# PowerSupply.net
KiCad netlist of a schematic drawn in Altium Designer
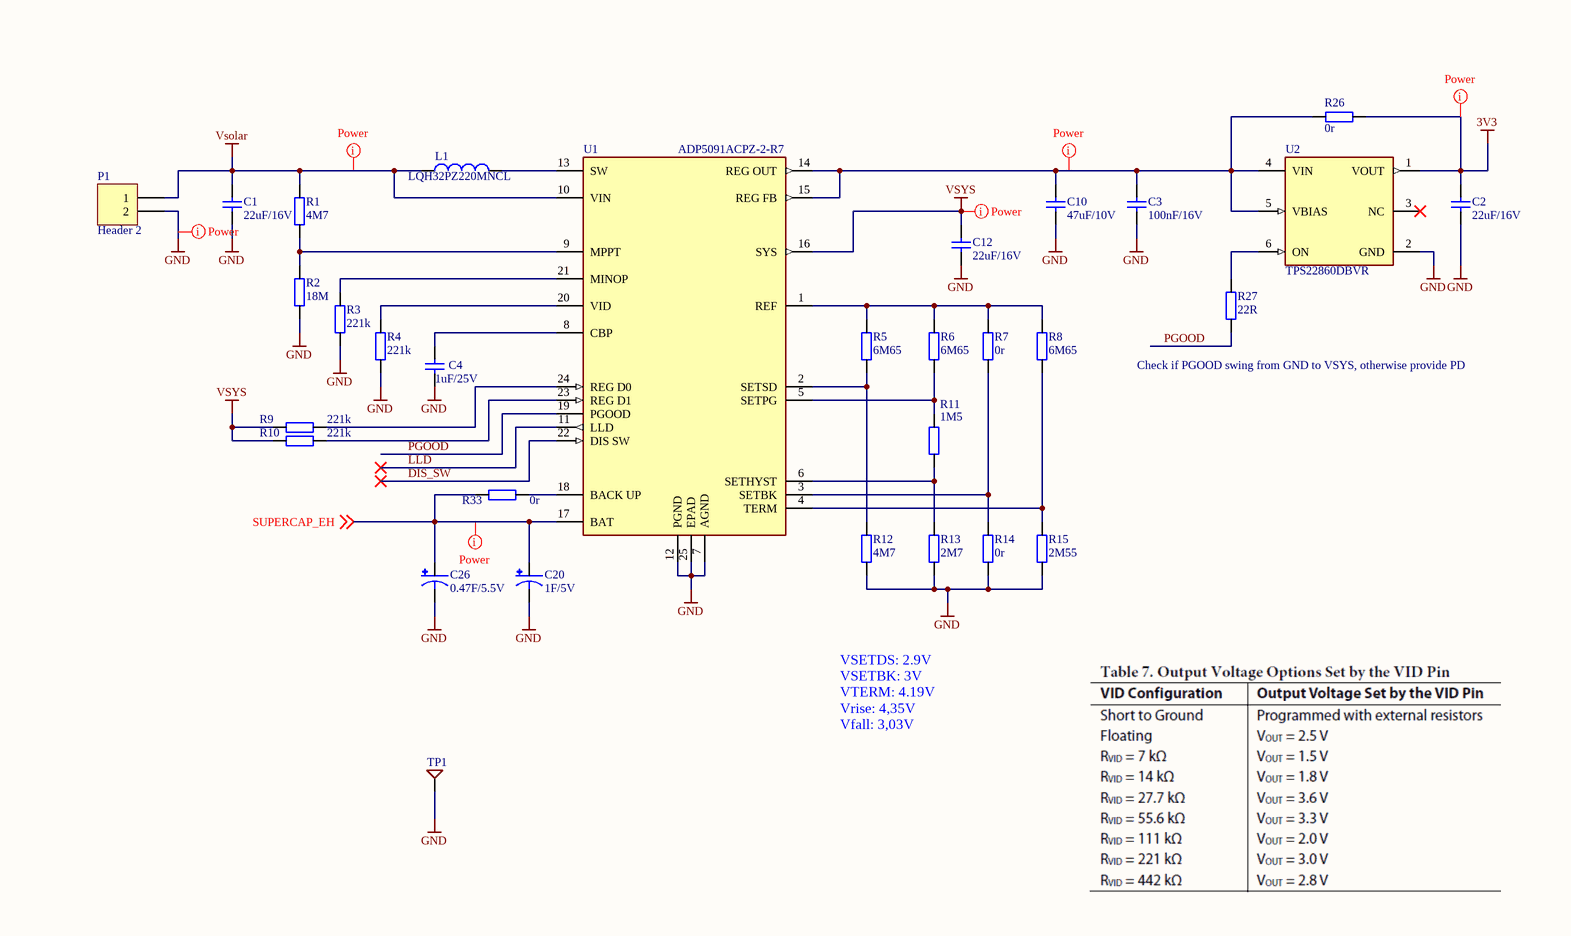
[diagram p0: PowerSupply.SchDoc, right]

(export (version "E")
  (design (tool "Eeschema 10.0.6"))
  (components
    (comp (ref "C1")
      (value "22uF/16V")
      (footprint "C0805")
      (description "22uF ±20% 16V Ceramic Capacitor X5R 0805")
      (fields
        (field (name "PARTNUMBER") "CL21A226MOQNNNE")
        (field (name "MANUFACTURER") "Samsung Electro-Mechanics")
      )
      (libsource (lib "DuPPa_Lib") (part "Cap_0805_22uF/16V"))
    )
    (comp (ref "C2")
      (value "22uF/16V")
      (footprint "C0805")
      (description "22uF ±20% 16V Ceramic Capacitor X5R 0805")
      (fields
        (field (name "PARTNUMBER") "CL21A226MOQNNNE")
        (field (name "MANUFACTURER") "Samsung Electro-Mechanics")
      )
      (libsource (lib "DuPPa_Lib") (part "Cap_0805_22uF/16V"))
    )
    (comp (ref "C3")
      (value "100nF/16V")
      (footprint "C0402")
      (description "16V 100nF X7R ±10% 0402 Multilayer Ceramic Capacitors MLCC - SMD/SMT ROHS")
      (fields
        (field (name "PARTNUMBER") "CL05B104KO5NNNC")
        (field (name "MANUFACTURER") "Samsung Electro-Mechanics")
      )
      (libsource (lib "DuPPa_Lib") (part "Cap_0402_100n/16V"))
    )
    (comp (ref "C4")
      (value "1uF/25V")
      (footprint "C0402")
      (description "1uF ±10% 25V Ceramic Capacitor X5R 0402")
      (fields
        (field (name "PARTNUMBER") "CL05A105KA5NQNC")
        (field (name "MANUFACTURER") "Samsung Electro-Mechanics")
      )
      (libsource (lib "DuPPa_Lib") (part "Cap_0402_1uF/25V"))
    )
    (comp (ref "C10")
      (value "47uF/10V")
      (footprint "C1206")
      (description "47uF ±20% 10V Ceramic Capacitor X5R 1206")
      (fields
        (field (name "PARTNUMBER") "CL31A476MPHNNNE")
        (field (name "MANUFACTURER") "Samsung Electro-Mechanics")
      )
      (libsource (lib "DuPPa_Lib") (part "Cap_1206_47uF/10V"))
    )
    (comp (ref "C12")
      (value "22uF/16V")
      (footprint "C0805")
      (description "22uF ±20% 16V Ceramic Capacitor X5R 0805")
      (fields
        (field (name "PARTNUMBER") "CL21A226MOQNNNE")
        (field (name "MANUFACTURER") "Samsung Electro-Mechanics")
      )
      (libsource (lib "DuPPa_Lib") (part "Cap_0805_22uF/16V"))
    )
    (comp (ref "C20")
      (value "1F/5V")
      (footprint "DGH105Q5R5")
      (description "DGH Series 5.5 v 1.0 F 17x17x8.5mm LS=12mm Radial Super Capacitor")
      (fields (field (name "VOLTAGE") "5V") (field (name "MANUFACTURER") "CDE Illinois Capacitor"))
      (libsource (lib "DuPPa_Lib") (part "SuperCap_1F/5V"))
    )
    (comp (ref "C26")
      (value "0.47F/5.5V")
      (footprint "SUPCAP_D20mm")
      (description "Super cap D=20mm H=8mm")
      (fields (field (name "VOLTAGE") "5.5V") (field (name "Comment") "SuperCap_0.47F/5.5V"))
      (libsource (lib "DuPPa_Lib") (part "SuperCap_0.47F/5.5V"))
    )
    (comp (ref "L1")
      (value "Inductor_22uH_550mA")
      (footprint "FP-LQH32PB_NC-MFG")
      (description "550mA 22uH ±20% 685mΩ 650mA 1210 Fixed Inductors RoHS")
      (fields (field (name "MANUFACTURER") "Murata") (field (name "PART NUMBER") "LQH32PZ220MNCL"))
      (libsource (lib "DuPPa_Lib") (part "Inductor_22uH_550mA"))
    )
    (comp (ref "P1")
      (value "Header 2")
      (footprint "HDR1X2")
      (description "Header, 2-Pin")
      (libsource (lib "DuPPa_Lib") (part "Header 2"))
    )
    (comp (ref "R1")
      (value "4M7")
      (footprint "R0402")
      (description "4.7MΩ ±1% 62.5mW 0402 Thick Film Resistor")
      (fields (field (name "PARTNUMBER") "0402WGF4704TCE") (field (name "MANUFACTURER") "UNI-ROYAL"))
      (libsource (lib "DuPPa_Lib") (part "R_R0402_4M7"))
    )
    (comp (ref "R2")
      (value "18M")
      (footprint "R0402")
      (description "0402, 1% ,63mW")
      (fields (field (name "PARTNUMBER") "0402WGF1805TCE") (field (name "MANUFACTURER") "UNI-ROYAL"))
      (libsource (lib "DuPPa_Lib") (part "R_R0402_18M"))
    )
    (comp (ref "R3")
      (value "221k")
      (footprint "R0402")
      (description "221kΩ ±1% 62.5mW 0402 Thick Film Resistor")
      (fields (field (name "PARTNUMBER") "0402WGF2213TCE") (field (name "MANUFACTURER") "UNI-ROYAL"))
      (libsource (lib "DuPPa_Lib") (part "R_R0402_221k"))
    )
    (comp (ref "R4")
      (value "221k")
      (footprint "R0402")
      (description "221kΩ ±1% 62.5mW 0402 Thick Film Resistor")
      (fields (field (name "PARTNUMBER") "0402WGF2213TCE") (field (name "MANUFACTURER") "UNI-ROYAL"))
      (libsource (lib "DuPPa_Lib") (part "R_R0402_221k"))
    )
    (comp (ref "R5")
      (value "6M65")
      (footprint "R0402")
      (description "6.65MΩ ±1% 62.5mW 0402 Thick Film Resistor")
      (fields (field (name "PARTNUMBER") "0402WGF6654TCE") (field (name "MANUFACTURER") "UNI-ROYAL"))
      (libsource (lib "DuPPa_Lib") (part "R_R0402_6M65"))
    )
    (comp (ref "R6")
      (value "6M65")
      (footprint "R0402")
      (description "6.65MΩ ±1% 62.5mW 0402 Thick Film Resistor")
      (fields (field (name "PARTNUMBER") "0402WGF6654TCE") (field (name "MANUFACTURER") "UNI-ROYAL"))
      (libsource (lib "DuPPa_Lib") (part "R_R0402_6M65"))
    )
    (comp (ref "R7")
      (value "0r")
      (footprint "R0402")
      (description "0Ω 62.5mW 50V Thick Film Resistor ±5% 0402 Chip Resistor - Surface Mount ROHS")
      (fields (field (name "PARTNUMBER") "0402WGJ0000TCE") (field (name "MANUFACTURER") "UNI-ROYAL"))
      (libsource (lib "DuPPa_Lib") (part "R_R0402_0R"))
    )
    (comp (ref "R8")
      (value "6M65")
      (footprint "R0402")
      (description "6.65MΩ ±1% 62.5mW 0402 Thick Film Resistor")
      (fields (field (name "PARTNUMBER") "0402WGF6654TCE") (field (name "MANUFACTURER") "UNI-ROYAL"))
      (libsource (lib "DuPPa_Lib") (part "R_R0402_6M65"))
    )
    (comp (ref "R9")
      (value "221k")
      (footprint "R0402")
      (description "221kΩ ±1% 62.5mW 0402 Thick Film Resistor")
      (fields (field (name "PARTNUMBER") "0402WGF2213TCE") (field (name "MANUFACTURER") "UNI-ROYAL"))
      (libsource (lib "DuPPa_Lib") (part "R_R0402_221k"))
    )
    (comp (ref "R10")
      (value "221k")
      (footprint "R0402")
      (description "221kΩ ±1% 62.5mW 0402 Thick Film Resistor")
      (fields (field (name "PARTNUMBER") "0402WGF2213TCE") (field (name "MANUFACTURER") "UNI-ROYAL"))
      (libsource (lib "DuPPa_Lib") (part "R_R0402_221k"))
    )
    (comp (ref "R11")
      (value "1M5")
      (footprint "R0402")
      (description "1.5MΩ ±1% 62.5mW 0402 Thick Film Resistor")
      (fields (field (name "PARTNUMBER") "0402WGF1504TCE") (field (name "MANUFACTURER") "UNI-ROYAL"))
      (libsource (lib "DuPPa_Lib") (part "R_R0402_1M5"))
    )
    (comp (ref "R12")
      (value "4M7")
      (footprint "R0402")
      (description "4.7MΩ ±1% 62.5mW 0402 Thick Film Resistor")
      (fields (field (name "PARTNUMBER") "0402WGF4704TCE") (field (name "MANUFACTURER") "UNI-ROYAL"))
      (libsource (lib "DuPPa_Lib") (part "R_R0402_4M7"))
    )
    (comp (ref "R13")
      (value "2M7")
      (footprint "R0402")
      (description "2.7MΩ ±1% 62.5mW 0402 Thick Film Resistor")
      (fields (field (name "PARTNUMBER") "0402WGF2704TCE") (field (name "MANUFACTURER") "UNI-ROYAL"))
      (libsource (lib "DuPPa_Lib") (part "R_R0402_2M7"))
    )
    (comp (ref "R14")
      (value "0r")
      (footprint "R0402")
      (description "0Ω 62.5mW 50V Thick Film Resistor ±5% 0402 Chip Resistor - Surface Mount ROHS")
      (fields (field (name "PARTNUMBER") "0402WGJ0000TCE") (field (name "MANUFACTURER") "UNI-ROYAL"))
      (libsource (lib "DuPPa_Lib") (part "R_R0402_0R"))
    )
    (comp (ref "R15")
      (value "2M55")
      (footprint "R0402")
      (description "2.55MΩ ±1% 62.5mW 0402 Thick Film Resistor")
      (fields (field (name "PARTNUMBER") "0402WGF2554TCE") (field (name "MANUFACTURER") "UNI-ROYAL"))
      (libsource (lib "DuPPa_Lib") (part "R_R0402_2M55"))
    )
    (comp (ref "R26")
      (value "0r")
      (footprint "R0402")
      (description "0Ω 62.5mW 50V Thick Film Resistor ±5% 0402 Chip Resistor - Surface Mount ROHS")
      (fields (field (name "PARTNUMBER") "0402WGJ0000TCE") (field (name "MANUFACTURER") "UNI-ROYAL"))
      (libsource (lib "DuPPa_Lib") (part "R_R0402_0R"))
    )
    (comp (ref "R27")
      (value "22R")
      (footprint "R0402")
      (description "22Ω ±1% 62.5mW 0402 Thick Film Resistor")
      (fields (field (name "PARTNUMBER") "0402WGF220JTCE") (field (name "MANUFACTURER") "UNI-ROYAL"))
      (libsource (lib "DuPPa_Lib") (part "R_R0402_22R"))
    )
    (comp (ref "R33")
      (value "0r")
      (footprint "R0402")
      (description "0Ω 62.5mW 50V Thick Film Resistor ±5% 0402 Chip Resistor - Surface Mount ROHS")
      (fields (field (name "PARTNUMBER") "0402WGJ0000TCE") (field (name "MANUFACTURER") "UNI-ROYAL"))
      (libsource (lib "DuPPa_Lib") (part "R_R0402_0R"))
    )
    (comp (ref "TP1")
      (value "TestPoint Trough Hole")
      (footprint "TestP-TH-1.32mm")
      (fields (field (name "PARTNUMBER") "RS-200-208"))
      (libsource (lib "DuPPa_Lib") (part "TestPoint-TH"))
    )
    (comp (ref "U1")
      (value "ADP5091ACPZ-2-R7")
      (footprint "FP-CP-24-14-IPC_B")
      (fields (field (name "MANUFACTURER") "Analog Devices"))
      (libsource (lib "DuPPa_Lib") (part "ADP5091ACPZ-2-R7"))
    )
    (comp (ref "U2")
      (value "TPS22860DBVR")
      (footprint "SOT-23-6")
      (description "Ultra-Low Leakage Current Single-Channel Load Switch")
      (fields (field (name "MANUFACTURER") "Texas Instruments"))
      (libsource (lib "DuPPa_Lib") (part "TPS22860DBVR"))
    )
  )
  (nets
    (net (code "1") (name "/DIS_SW") (class "Default")
      (node (ref "U1") (pin "22") (pinfunction "DIS_SW_22") (pintype "input+no_connect"))
    )
    (net (code "2") (name "/LLD") (class "Default")
      (node (ref "U1") (pin "11") (pinfunction "LLD_11") (pintype "output+no_connect"))
    )
    (net (code "3") (name "/PGOOD") (class "Default")
      (node (ref "R27") (pin "2") (pinfunction "2_2") (pintype "passive"))
      (node (ref "U1") (pin "19") (pinfunction "PGOOD_19") (pintype "power_in"))
    )
    (net (code "4") (name "3V3") (class "Default")
      (node (ref "C2") (pin "1") (pinfunction "1_1") (pintype "passive"))
      (node (ref "R26") (pin "1") (pinfunction "1_1") (pintype "passive"))
      (node (ref "U2") (pin "1") (pinfunction "VOUT_1") (pintype "output"))
    )
    (net (code "5") (name "GND") (class "Default")
      (node (ref "C1") (pin "2") (pinfunction "2_2") (pintype "passive"))
      (node (ref "C10") (pin "2") (pinfunction "2_2") (pintype "passive"))
      (node (ref "C12") (pin "2") (pinfunction "2_2") (pintype "passive"))
      (node (ref "C2") (pin "2") (pinfunction "2_2") (pintype "passive"))
      (node (ref "C20") (pin "-") (pinfunction "-_-") (pintype "passive"))
      (node (ref "C26") (pin "-") (pinfunction "-_-") (pintype "passive"))
      (node (ref "C3") (pin "2") (pinfunction "2_2") (pintype "passive"))
      (node (ref "C4") (pin "2") (pinfunction "2_2") (pintype "passive"))
      (node (ref "P1") (pin "2") (pinfunction "2_2") (pintype "passive"))
      (node (ref "R12") (pin "1") (pinfunction "1_1") (pintype "passive"))
      (node (ref "R13") (pin "1") (pinfunction "1_1") (pintype "passive"))
      (node (ref "R14") (pin "1") (pinfunction "1_1") (pintype "passive"))
      (node (ref "R15") (pin "1") (pinfunction "1_1") (pintype "passive"))
      (node (ref "R2") (pin "1") (pinfunction "1_1") (pintype "passive"))
      (node (ref "R3") (pin "1") (pinfunction "1_1") (pintype "passive"))
      (node (ref "R4") (pin "1") (pinfunction "1_1") (pintype "passive"))
      (node (ref "TP1") (pin "0") (pinfunction "TP_0") (pintype "passive"))
      (node (ref "U1") (pin "12") (pinfunction "PGND_12") (pintype "power_in"))
      (node (ref "U1") (pin "25") (pinfunction "EPAD_25") (pintype "power_in"))
      (node (ref "U1") (pin "7") (pinfunction "AGND_7") (pintype "power_in"))
      (node (ref "U2") (pin "2") (pinfunction "GND_2") (pintype "power_in"))
    )
    (net (code "6") (name "Net-(U1-BACK_UP)") (class "Default")
      (node (ref "R33") (pin "1") (pinfunction "1_1") (pintype "passive"))
      (node (ref "U1") (pin "18") (pinfunction "BACK_UP_18") (pintype "power_in"))
    )
    (net (code "7") (name "Net-(U1-CBP)") (class "Default")
      (node (ref "C4") (pin "1") (pinfunction "1_1") (pintype "passive"))
      (node (ref "U1") (pin "8") (pinfunction "CBP_8") (pintype "passive"))
    )
    (net (code "8") (name "Net-(U1-MINOP)") (class "Default")
      (node (ref "R3") (pin "2") (pinfunction "2_2") (pintype "passive"))
      (node (ref "U1") (pin "21") (pinfunction "MINOP_21") (pintype "power_in"))
    )
    (net (code "9") (name "Net-(U1-MPPT)") (class "Default")
      (node (ref "R1") (pin "1") (pinfunction "1_1") (pintype "passive"))
      (node (ref "R2") (pin "2") (pinfunction "2_2") (pintype "passive"))
      (node (ref "U1") (pin "9") (pinfunction "MPPT_9") (pintype "passive"))
    )
    (net (code "10") (name "Net-(U1-REF)") (class "Default")
      (node (ref "R5") (pin "2") (pinfunction "2_2") (pintype "passive"))
      (node (ref "R6") (pin "2") (pinfunction "2_2") (pintype "passive"))
      (node (ref "R7") (pin "2") (pinfunction "2_2") (pintype "passive"))
      (node (ref "R8") (pin "2") (pinfunction "2_2") (pintype "passive"))
      (node (ref "U1") (pin "1") (pinfunction "REF_1") (pintype "power_in"))
    )
    (net (code "11") (name "Net-(U1-REG_D0)") (class "Default")
      (node (ref "R9") (pin "1") (pinfunction "1_1") (pintype "passive"))
      (node (ref "U1") (pin "24") (pinfunction "REG_D0_24") (pintype "input"))
    )
    (net (code "12") (name "Net-(U1-REG_D1)") (class "Default")
      (node (ref "R10") (pin "1") (pinfunction "1_1") (pintype "passive"))
      (node (ref "U1") (pin "23") (pinfunction "REG_D1_23") (pintype "input"))
    )
    (net (code "13") (name "Net-(U1-REG_FB)") (class "Default")
      (node (ref "C10") (pin "1") (pinfunction "1_1") (pintype "passive"))
      (node (ref "C3") (pin "1") (pinfunction "1_1") (pintype "passive"))
      (node (ref "R26") (pin "2") (pinfunction "2_2") (pintype "passive"))
      (node (ref "U1") (pin "14") (pinfunction "REG_OUT_14") (pintype "output"))
      (node (ref "U1") (pin "15") (pinfunction "REG_FB_15") (pintype "output"))
      (node (ref "U2") (pin "4") (pinfunction "VIN_4") (pintype "power_in"))
      (node (ref "U2") (pin "5") (pinfunction "VBIAS_5") (pintype "input"))
    )
    (net (code "14") (name "Net-(U1-SETBK)") (class "Default")
      (node (ref "R14") (pin "2") (pinfunction "2_2") (pintype "passive"))
      (node (ref "R7") (pin "1") (pinfunction "1_1") (pintype "passive"))
      (node (ref "U1") (pin "3") (pinfunction "SETBK_3") (pintype "passive"))
    )
    (net (code "15") (name "Net-(U1-SETHYST)") (class "Default")
      (node (ref "R11") (pin "1") (pinfunction "1_1") (pintype "passive"))
      (node (ref "R13") (pin "2") (pinfunction "2_2") (pintype "passive"))
      (node (ref "U1") (pin "6") (pinfunction "SETHYST_6") (pintype "passive"))
    )
    (net (code "16") (name "Net-(U1-SETPG)") (class "Default")
      (node (ref "R11") (pin "2") (pinfunction "2_2") (pintype "passive"))
      (node (ref "R6") (pin "1") (pinfunction "1_1") (pintype "passive"))
      (node (ref "U1") (pin "5") (pinfunction "SETPG_5") (pintype "passive"))
    )
    (net (code "17") (name "Net-(U1-SETSD)") (class "Default")
      (node (ref "R12") (pin "2") (pinfunction "2_2") (pintype "passive"))
      (node (ref "R5") (pin "1") (pinfunction "1_1") (pintype "passive"))
      (node (ref "U1") (pin "2") (pinfunction "SETSD_2") (pintype "passive"))
    )
    (net (code "18") (name "Net-(U1-SW)") (class "Default")
      (node (ref "L1") (pin "2") (pinfunction "2_2") (pintype "passive"))
      (node (ref "U1") (pin "13") (pinfunction "SW_13") (pintype "passive"))
    )
    (net (code "19") (name "Net-(U1-TERM)") (class "Default")
      (node (ref "R15") (pin "2") (pinfunction "2_2") (pintype "passive"))
      (node (ref "R8") (pin "1") (pinfunction "1_1") (pintype "passive"))
      (node (ref "U1") (pin "4") (pinfunction "TERM_4") (pintype "passive"))
    )
    (net (code "20") (name "Net-(U1-VID)") (class "Default")
      (node (ref "R4") (pin "2") (pinfunction "2_2") (pintype "passive"))
      (node (ref "U1") (pin "20") (pinfunction "VID_20") (pintype "power_in"))
    )
    (net (code "21") (name "Net-(U2-ON)") (class "Default")
      (node (ref "R27") (pin "1") (pinfunction "1_1") (pintype "passive"))
      (node (ref "U2") (pin "6") (pinfunction "ON_6") (pintype "input"))
    )
    (net (code "22") (name "SUPERCAP_EH") (class "Default")
      (node (ref "C20") (pin "+") (pinfunction "+_+") (pintype "passive"))
      (node (ref "C26") (pin "+") (pinfunction "+_+") (pintype "passive"))
      (node (ref "R33") (pin "2") (pinfunction "2_2") (pintype "passive"))
      (node (ref "U1") (pin "17") (pinfunction "BAT_17") (pintype "power_in"))
    )
    (net (code "23") (name "VSYS") (class "Default")
      (node (ref "C12") (pin "1") (pinfunction "1_1") (pintype "passive"))
      (node (ref "R10") (pin "2") (pinfunction "2_2") (pintype "passive"))
      (node (ref "R9") (pin "2") (pinfunction "2_2") (pintype "passive"))
      (node (ref "U1") (pin "16") (pinfunction "SYS_16") (pintype "output"))
    )
    (net (code "24") (name "Vsolar") (class "Default")
      (node (ref "C1") (pin "1") (pinfunction "1_1") (pintype "passive"))
      (node (ref "L1") (pin "1") (pinfunction "1_1") (pintype "passive"))
      (node (ref "P1") (pin "1") (pinfunction "1_1") (pintype "passive"))
      (node (ref "R1") (pin "2") (pinfunction "2_2") (pintype "passive"))
      (node (ref "U1") (pin "10") (pinfunction "VIN_10") (pintype "power_in"))
    )
    (net (code "25") (name "unconnected-(U2-NC-Pad3)") (class "Default")
      (node (ref "U2") (pin "3") (pinfunction "NC_3") (pintype "passive+no_connect"))
    )
  )
)
